# AdamDynamic_VCA-001.net
KiCad netlist of a schematic drawn in Altium Designer
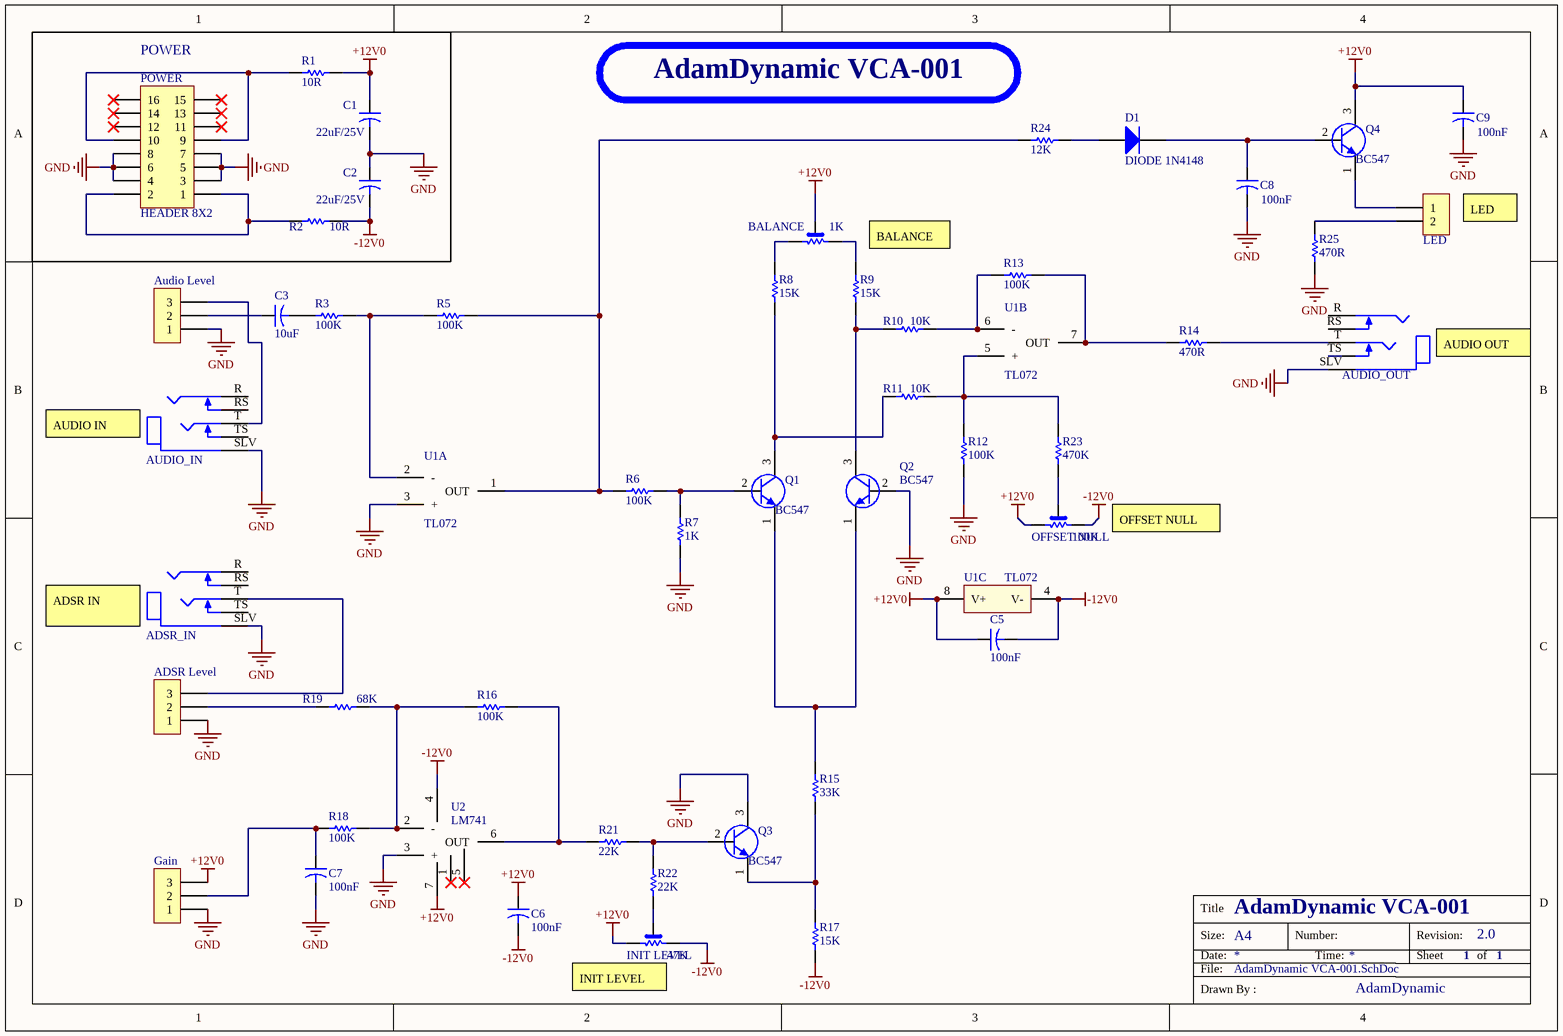
[diagram p0: AdamDynamic VCA-001.SchDoc]

(export (version "E")
  (design (tool "Eeschema 10.0.6"))
  (components
    (comp (ref "ADSR Level")
      (value "SCREW TERMINAL 3WAY")
      (footprint "SCREW TERMINAL 3WAY")
      (description "SCREW TERMINAL 3WAY 5.08mm")
      (libsource (lib "Integrated_Library1") (part "SCREW TERMINAL 3WAY"))
    )
    (comp (ref "ADSR_IN")
      (value "N114BPCX")
      (footprint "SWITCHCRAFT_N114BPCX")
      (description "Conn 1/4'' Phone Jack F 3 POS Solder ST Thru-Hole 5 Terminal 1 Port")
      (libsource (lib "112APCX") (part "N114BPCX"))
    )
    (comp (ref "Audio Level")
      (value "SCREW TERMINAL 3WAY")
      (footprint "SCREW TERMINAL 3WAY")
      (description "SCREW TERMINAL 3WAY 5.08mm")
      (libsource (lib "Integrated_Library1") (part "SCREW TERMINAL 3WAY"))
    )
    (comp (ref "AUDIO_IN")
      (value "N114BPCX")
      (footprint "SWITCHCRAFT_N114BPCX")
      (description "Conn 1/4'' Phone Jack F 3 POS Solder ST Thru-Hole 5 Terminal 1 Port")
      (libsource (lib "112APCX") (part "N114BPCX"))
    )
    (comp (ref "AUDIO_OUT")
      (value "N114BPCX")
      (footprint "SWITCHCRAFT_N114BPCX")
      (description "Conn 1/4'' Phone Jack F 3 POS Solder ST Thru-Hole 5 Terminal 1 Port")
      (libsource (lib "112APCX") (part "N114BPCX"))
    )
    (comp (ref "BALANCE")
      (value "1K")
      (footprint "RES VAR SQ")
      (description "Multiturn")
      (libsource (lib "Integrated_Library1") (part "ResTrimpot"))
    )
    (comp (ref "C1")
      (value "22uF/25V")
      (footprint "CAP 5X11")
      (libsource (lib "Integrated_Library1") (part "Capacitor Polar"))
    )
    (comp (ref "C2")
      (value "22uF/25V")
      (footprint "CAP 5X11")
      (libsource (lib "Integrated_Library1") (part "Capacitor Polar"))
    )
    (comp (ref "C3")
      (value "10uF")
      (footprint "CAP 5X11")
      (libsource (lib "Integrated_Library1") (part "Capacitor Polar"))
    )
    (comp (ref "C5")
      (value "100nF")
      (footprint "CAP RAD-0.3")
      (libsource (lib "Integrated_Library1") (part "Capacitor Polar"))
    )
    (comp (ref "C6")
      (value "100nF")
      (footprint "CAP RAD-0.3")
      (libsource (lib "Integrated_Library1") (part "Capacitor Polar"))
    )
    (comp (ref "C7")
      (value "100nF")
      (footprint "CAP RAD-0.3")
      (libsource (lib "Integrated_Library1") (part "Capacitor Polar"))
    )
    (comp (ref "C8")
      (value "100nF")
      (footprint "CAP RAD-0.3")
      (libsource (lib "Integrated_Library1") (part "Capacitor Polar"))
    )
    (comp (ref "C9")
      (value "100nF")
      (footprint "CAP RAD-0.3")
      (libsource (lib "Integrated_Library1") (part "Capacitor Polar"))
    )
    (comp (ref "D1")
      (value "DIODE 1N4148")
      (footprint "DO-35")
      (description "Small Signal Fast Switching Diodes")
      (libsource (lib "Integrated_Library1") (part "DIODE 1N4148"))
    )
    (comp (ref "Gain")
      (value "SCREW TERMINAL 3WAY")
      (footprint "SCREW TERMINAL 3WAY")
      (description "SCREW TERMINAL 3WAY 5.08mm")
      (libsource (lib "Integrated_Library1") (part "SCREW TERMINAL 3WAY"))
    )
    (comp (ref "INIT LEVEL")
      (value "47K")
      (footprint "RES VAR SQ")
      (description "Multiturn")
      (libsource (lib "Integrated_Library1") (part "ResTrimpot"))
    )
    (comp (ref "LED")
      (value "SCREW TERMINAL 2WAY")
      (footprint "SCREW TERMINAL 2WAY")
      (description "SCREW TERMINAL 2WAY 5.08mm")
      (libsource (lib "Integrated_Library1") (part "SCREW TERMINAL 2WAY"))
    )
    (comp (ref "OFFSET NULL")
      (value "100K")
      (footprint "RES VAR")
      (description "Multiturn")
      (libsource (lib "Integrated_Library1") (part "ResTrimpot"))
    )
    (comp (ref "POWER")
      (value "HEADER 8X2")
      (footprint "HEADER 8X2")
      (libsource (lib "Integrated_Library1") (part "HEADER 8X2"))
    )
    (comp (ref "Q1")
      (value "BC547")
      (footprint "TO92")
      (description "NPN Epitaxial Silicon Transistor")
      (libsource (lib "Integrated_Library1") (part "BC547"))
    )
    (comp (ref "Q2")
      (value "BC547")
      (footprint "TO92")
      (description "NPN Epitaxial Silicon Transistor")
      (libsource (lib "Integrated_Library1") (part "BC547"))
    )
    (comp (ref "Q3")
      (value "BC547")
      (footprint "TO92")
      (description "NPN Epitaxial Silicon Transistor")
      (libsource (lib "Integrated_Library1") (part "BC547"))
    )
    (comp (ref "Q4")
      (value "BC547")
      (footprint "TO92")
      (description "NPN Epitaxial Silicon Transistor")
      (libsource (lib "Integrated_Library1") (part "BC547"))
    )
    (comp (ref "R1")
      (value "10R")
      (footprint "RES 6.2 x 0.5 x 2.3")
      (description "Resistor")
      (fields (field (name "PUBLISHER") "Altium Limited"))
      (libsource (lib "Schlib1") (part "Res2"))
    )
    (comp (ref "R2")
      (value "10R")
      (footprint "RES 6.2 x 0.5 x 2.3")
      (description "Resistor")
      (fields (field (name "PUBLISHER") "Altium Limited"))
      (libsource (lib "Schlib1") (part "Res2"))
    )
    (comp (ref "R3")
      (value "100K")
      (footprint "RES 6.2 x 0.5 x 2.3")
      (description "Resistor")
      (fields (field (name "PUBLISHER") "Altium Limited"))
      (libsource (lib "Schlib1") (part "Res2"))
    )
    (comp (ref "R5")
      (value "100K")
      (footprint "RES 6.2 x 0.5 x 2.3")
      (description "Resistor")
      (fields (field (name "PUBLISHER") "Altium Limited"))
      (libsource (lib "Schlib1") (part "Res2"))
    )
    (comp (ref "R6")
      (value "100K")
      (footprint "RES 6.2 x 0.5 x 2.3")
      (description "Resistor")
      (fields (field (name "PUBLISHER") "Altium Limited"))
      (libsource (lib "Schlib1") (part "Res2"))
    )
    (comp (ref "R7")
      (value "1K")
      (footprint "RES 6.2 x 0.5 x 2.3")
      (description "Resistor")
      (fields (field (name "PUBLISHER") "Altium Limited"))
      (libsource (lib "Schlib1") (part "Res2"))
    )
    (comp (ref "R8")
      (value "15K")
      (footprint "RES 6.2 x 0.5 x 2.3")
      (description "Resistor")
      (fields (field (name "PUBLISHER") "Altium Limited"))
      (libsource (lib "Schlib1") (part "Res2"))
    )
    (comp (ref "R9")
      (value "15K")
      (footprint "RES 6.2 x 0.5 x 2.3")
      (description "Resistor")
      (fields (field (name "PUBLISHER") "Altium Limited"))
      (libsource (lib "Schlib1") (part "Res2"))
    )
    (comp (ref "R10")
      (value "10K")
      (footprint "RES 6.2 x 0.5 x 2.3")
      (description "Resistor")
      (fields (field (name "PUBLISHER") "Altium Limited"))
      (libsource (lib "Schlib1") (part "Res2"))
    )
    (comp (ref "R11")
      (value "10K")
      (footprint "RES 6.2 x 0.5 x 2.3")
      (description "Resistor")
      (fields (field (name "PUBLISHER") "Altium Limited"))
      (libsource (lib "Schlib1") (part "Res2"))
    )
    (comp (ref "R12")
      (value "100K")
      (footprint "RES 6.2 x 0.5 x 2.3")
      (description "Resistor")
      (fields (field (name "PUBLISHER") "Altium Limited"))
      (libsource (lib "Schlib1") (part "Res2"))
    )
    (comp (ref "R13")
      (value "100K")
      (footprint "RES 6.2 x 0.5 x 2.3")
      (description "Resistor")
      (fields (field (name "PUBLISHER") "Altium Limited"))
      (libsource (lib "Schlib1") (part "Res2"))
    )
    (comp (ref "R14")
      (value "470R")
      (footprint "RES 6.2 x 0.5 x 2.3")
      (description "Resistor")
      (fields (field (name "PUBLISHER") "Altium Limited"))
      (libsource (lib "Schlib1") (part "Res2"))
    )
    (comp (ref "R15")
      (value "33K")
      (footprint "RES 6.2 x 0.5 x 2.3")
      (description "Resistor")
      (fields (field (name "PUBLISHER") "Altium Limited"))
      (libsource (lib "Schlib1") (part "Res2"))
    )
    (comp (ref "R16")
      (value "100K")
      (footprint "RES 6.2 x 0.5 x 2.3")
      (description "Resistor")
      (fields (field (name "PUBLISHER") "Altium Limited"))
      (libsource (lib "Schlib1") (part "Res2"))
    )
    (comp (ref "R17")
      (value "15K")
      (footprint "RES 6.2 x 0.5 x 2.3")
      (description "Resistor")
      (fields (field (name "PUBLISHER") "Altium Limited"))
      (libsource (lib "Schlib1") (part "Res2"))
    )
    (comp (ref "R18")
      (value "100K")
      (footprint "RES 6.2 x 0.5 x 2.3")
      (description "Resistor")
      (fields (field (name "PUBLISHER") "Altium Limited"))
      (libsource (lib "Schlib1") (part "Res2"))
    )
    (comp (ref "R19")
      (value "68K")
      (footprint "RES 6.2 x 0.5 x 2.3")
      (description "Resistor")
      (fields (field (name "PUBLISHER") "Altium Limited"))
      (libsource (lib "Schlib1") (part "Res2"))
    )
    (comp (ref "R21")
      (value "22K")
      (footprint "RES 6.2 x 0.5 x 2.3")
      (description "Resistor")
      (fields (field (name "PUBLISHER") "Altium Limited"))
      (libsource (lib "Schlib1") (part "Res2"))
    )
    (comp (ref "R22")
      (value "22K")
      (footprint "RES 6.2 x 0.5 x 2.3")
      (description "Resistor")
      (fields (field (name "PUBLISHER") "Altium Limited"))
      (libsource (lib "Schlib1") (part "Res2"))
    )
    (comp (ref "R23")
      (value "470K")
      (footprint "RES 6.2 x 0.5 x 2.3")
      (description "Resistor")
      (fields (field (name "PUBLISHER") "Altium Limited"))
      (libsource (lib "Schlib1") (part "Res2"))
    )
    (comp (ref "R24")
      (value "12K")
      (footprint "RES 6.2 x 0.5 x 2.3")
      (description "Resistor")
      (fields (field (name "PUBLISHER") "Altium Limited"))
      (libsource (lib "Schlib1") (part "Res2"))
    )
    (comp (ref "R25")
      (value "470R")
      (footprint "RES 6.2 x 0.5 x 2.3")
      (description "Resistor")
      (fields (field (name "PUBLISHER") "Altium Limited"))
      (libsource (lib "Schlib1") (part "Res2"))
    )
    (comp (ref "U1")
      (value "TL072")
      (footprint "DIP 8 PIN")
      (description "Low-Noise FET-Input Operational Amplifiers")
      (libsource (lib "Integrated_Library1") (part "TL072"))
    )
    (comp (ref "U2")
      (value "LM741")
      (footprint "DIP 8 PIN")
      (libsource (lib "Integrated_Library1") (part "LM741"))
    )
  )
  (nets
    (net (code "1") (name "+12V0") (class "Default")
      (node (ref "BALANCE") (pin "2") (pinfunction "2_2") (pintype "passive"))
      (node (ref "C1") (pin "1") (pinfunction "1_1") (pintype "passive"))
      (node (ref "C5") (pin "1") (pinfunction "1_1") (pintype "passive"))
      (node (ref "C6") (pin "1") (pinfunction "1_1") (pintype "passive"))
      (node (ref "C9") (pin "1") (pinfunction "1_1") (pintype "passive"))
      (node (ref "Gain") (pin "3") (pinfunction "3_3") (pintype "passive"))
      (node (ref "INIT LEVEL") (pin "1") (pinfunction "1_1") (pintype "passive"))
      (node (ref "OFFSET NULL") (pin "1") (pinfunction "1_1") (pintype "passive"))
      (node (ref "Q4") (pin "3") (pinfunction "E_3") (pintype "passive"))
      (node (ref "R1") (pin "1") (pinfunction "1_1") (pintype "passive"))
      (node (ref "U1") (pin "8") (pinfunction "V+_8") (pintype "passive"))
      (node (ref "U2") (pin "7") (pintype "passive"))
    )
    (net (code "2") (name "-12V0") (class "Default")
      (node (ref "C2") (pin "2") (pinfunction "2_2") (pintype "passive"))
      (node (ref "C5") (pin "2") (pinfunction "2_2") (pintype "passive"))
      (node (ref "C6") (pin "2") (pinfunction "2_2") (pintype "passive"))
      (node (ref "INIT LEVEL") (pin "3") (pinfunction "3_3") (pintype "passive"))
      (node (ref "OFFSET NULL") (pin "3") (pinfunction "3_3") (pintype "passive"))
      (node (ref "R17") (pin "1") (pinfunction "1_1") (pintype "passive"))
      (node (ref "R2") (pin "1") (pinfunction "1_1") (pintype "passive"))
      (node (ref "U1") (pin "4") (pinfunction "V-_4") (pintype "passive"))
      (node (ref "U2") (pin "4") (pintype "passive"))
    )
    (net (code "3") (name "GND") (class "Default")
      (node (ref "ADSR Level") (pin "1") (pinfunction "1_1") (pintype "passive"))
      (node (ref "ADSR_IN") (pin "SLV") (pinfunction "SLEEVE_SLV") (pintype "passive"))
      (node (ref "AUDIO_IN") (pin "SLV") (pinfunction "SLEEVE_SLV") (pintype "passive"))
      (node (ref "AUDIO_OUT") (pin "SLV") (pinfunction "SLEEVE_SLV") (pintype "passive"))
      (node (ref "Audio Level") (pin "1") (pinfunction "1_1") (pintype "passive"))
      (node (ref "C1") (pin "2") (pinfunction "2_2") (pintype "passive"))
      (node (ref "C2") (pin "1") (pinfunction "1_1") (pintype "passive"))
      (node (ref "C7") (pin "2") (pinfunction "2_2") (pintype "passive"))
      (node (ref "C8") (pin "2") (pinfunction "2_2") (pintype "passive"))
      (node (ref "C9") (pin "2") (pinfunction "2_2") (pintype "passive"))
      (node (ref "Gain") (pin "1") (pinfunction "1_1") (pintype "passive"))
      (node (ref "POWER") (pin "3") (pinfunction "3_3") (pintype "passive"))
      (node (ref "POWER") (pin "4") (pinfunction "4_4") (pintype "passive"))
      (node (ref "POWER") (pin "5") (pinfunction "5_5") (pintype "passive"))
      (node (ref "POWER") (pin "6") (pinfunction "6_6") (pintype "passive"))
      (node (ref "POWER") (pin "7") (pinfunction "7_7") (pintype "passive"))
      (node (ref "POWER") (pin "8") (pinfunction "8_8") (pintype "passive"))
      (node (ref "Q2") (pin "2") (pinfunction "B_2") (pintype "passive"))
      (node (ref "Q3") (pin "3") (pinfunction "E_3") (pintype "passive"))
      (node (ref "R12") (pin "2") (pinfunction "2_2") (pintype "passive"))
      (node (ref "R25") (pin "2") (pinfunction "2_2") (pintype "passive"))
      (node (ref "R7") (pin "2") (pinfunction "2_2") (pintype "passive"))
      (node (ref "U1") (pin "3") (pinfunction "+_3") (pintype "passive"))
      (node (ref "U2") (pin "3") (pinfunction "+_3") (pintype "passive"))
    )
    (net (code "4") (name "Net-(ADSR Level-Pad2)") (class "Default")
      (node (ref "ADSR Level") (pin "2") (pinfunction "2_2") (pintype "passive"))
      (node (ref "R19") (pin "2") (pinfunction "2_2") (pintype "passive"))
    )
    (net (code "5") (name "Net-(ADSR_IN-TIP)") (class "Default")
      (node (ref "ADSR Level") (pin "3") (pinfunction "3_3") (pintype "passive"))
      (node (ref "ADSR_IN") (pin "T") (pinfunction "TIP_T") (pintype "passive"))
    )
    (net (code "6") (name "Net-(AUDIO_IN-TIP)") (class "Default")
      (node (ref "AUDIO_IN") (pin "T") (pinfunction "TIP_T") (pintype "passive"))
      (node (ref "Audio Level") (pin "3") (pinfunction "3_3") (pintype "passive"))
    )
    (net (code "7") (name "Net-(AUDIO_OUT-TIP)") (class "Default")
      (node (ref "AUDIO_OUT") (pin "T") (pinfunction "TIP_T") (pintype "passive"))
      (node (ref "R14") (pin "1") (pinfunction "1_1") (pintype "passive"))
    )
    (net (code "8") (name "Net-(Audio Level-Pad2)") (class "Default")
      (node (ref "Audio Level") (pin "2") (pinfunction "2_2") (pintype "passive"))
      (node (ref "C3") (pin "1") (pinfunction "1_1") (pintype "passive"))
    )
    (net (code "9") (name "Net-(BALANCE-Pad1)") (class "Default")
      (node (ref "BALANCE") (pin "1") (pinfunction "1_1") (pintype "passive"))
      (node (ref "R8") (pin "2") (pinfunction "2_2") (pintype "passive"))
    )
    (net (code "10") (name "Net-(BALANCE-Pad3)") (class "Default")
      (node (ref "BALANCE") (pin "3") (pinfunction "3_3") (pintype "passive"))
      (node (ref "R9") (pin "2") (pinfunction "2_2") (pintype "passive"))
    )
    (net (code "11") (name "Net-(C3-Pad2)") (class "Default")
      (node (ref "C3") (pin "2") (pinfunction "2_2") (pintype "passive"))
      (node (ref "R3") (pin "2") (pinfunction "2_2") (pintype "passive"))
    )
    (net (code "12") (name "Net-(C7-Pad1)") (class "Default")
      (node (ref "C7") (pin "1") (pinfunction "1_1") (pintype "passive"))
      (node (ref "Gain") (pin "2") (pinfunction "2_2") (pintype "passive"))
      (node (ref "R18") (pin "2") (pinfunction "2_2") (pintype "passive"))
    )
    (net (code "13") (name "Net-(D1-A)") (class "Default")
      (node (ref "D1") (pin "1") (pinfunction "A_1") (pintype "passive"))
      (node (ref "R24") (pin "1") (pinfunction "1_1") (pintype "passive"))
    )
    (net (code "14") (name "Net-(D1-K)") (class "Default")
      (node (ref "C8") (pin "1") (pinfunction "1_1") (pintype "passive"))
      (node (ref "D1") (pin "2") (pinfunction "K_2") (pintype "passive"))
      (node (ref "Q4") (pin "2") (pinfunction "B_2") (pintype "passive"))
    )
    (net (code "15") (name "Net-(INIT LEVEL-Pad2)") (class "Default")
      (node (ref "INIT LEVEL") (pin "2") (pinfunction "2_2") (pintype "passive"))
      (node (ref "R22") (pin "2") (pinfunction "2_2") (pintype "passive"))
    )
    (net (code "16") (name "Net-(LED-Pad2)") (class "Default")
      (node (ref "LED") (pin "2") (pinfunction "2_2") (pintype "passive"))
      (node (ref "R25") (pin "1") (pinfunction "1_1") (pintype "passive"))
    )
    (net (code "17") (name "Net-(OFFSET NULL-Pad2)") (class "Default")
      (node (ref "OFFSET NULL") (pin "2") (pinfunction "2_2") (pintype "passive"))
      (node (ref "R23") (pin "2") (pinfunction "2_2") (pintype "passive"))
    )
    (net (code "18") (name "Net-(POWER-Pad1)") (class "Default")
      (node (ref "POWER") (pin "1") (pinfunction "1_1") (pintype "passive"))
      (node (ref "POWER") (pin "2") (pinfunction "2_2") (pintype "passive"))
      (node (ref "R2") (pin "2") (pinfunction "2_2") (pintype "passive"))
    )
    (net (code "19") (name "Net-(POWER-Pad10)") (class "Default")
      (node (ref "POWER") (pin "10") (pinfunction "10_10") (pintype "passive"))
      (node (ref "POWER") (pin "9") (pinfunction "9_9") (pintype "passive"))
      (node (ref "R1") (pin "2") (pinfunction "2_2") (pintype "passive"))
    )
    (net (code "20") (name "Net-(Q1-B)") (class "Default")
      (node (ref "Q1") (pin "2") (pinfunction "B_2") (pintype "passive"))
      (node (ref "R6") (pin "1") (pinfunction "1_1") (pintype "passive"))
      (node (ref "R7") (pin "1") (pinfunction "1_1") (pintype "passive"))
    )
    (net (code "21") (name "Net-(Q1-C)") (class "Default")
      (node (ref "Q1") (pin "1") (pinfunction "C_1") (pintype "passive"))
      (node (ref "Q2") (pin "1") (pinfunction "C_1") (pintype "passive"))
      (node (ref "R15") (pin "2") (pinfunction "2_2") (pintype "passive"))
    )
    (net (code "22") (name "Net-(Q1-E)") (class "Default")
      (node (ref "Q1") (pin "3") (pinfunction "E_3") (pintype "passive"))
      (node (ref "R11") (pin "2") (pinfunction "2_2") (pintype "passive"))
      (node (ref "R8") (pin "1") (pinfunction "1_1") (pintype "passive"))
    )
    (net (code "23") (name "Net-(Q2-E)") (class "Default")
      (node (ref "Q2") (pin "3") (pinfunction "E_3") (pintype "passive"))
      (node (ref "R10") (pin "2") (pinfunction "2_2") (pintype "passive"))
      (node (ref "R9") (pin "1") (pinfunction "1_1") (pintype "passive"))
    )
    (net (code "24") (name "Net-(Q3-B)") (class "Default")
      (node (ref "Q3") (pin "2") (pinfunction "B_2") (pintype "passive"))
      (node (ref "R21") (pin "1") (pinfunction "1_1") (pintype "passive"))
      (node (ref "R22") (pin "1") (pinfunction "1_1") (pintype "passive"))
    )
    (net (code "25") (name "Net-(Q3-C)") (class "Default")
      (node (ref "Q3") (pin "1") (pinfunction "C_1") (pintype "passive"))
      (node (ref "R15") (pin "1") (pinfunction "1_1") (pintype "passive"))
      (node (ref "R17") (pin "2") (pinfunction "2_2") (pintype "passive"))
    )
    (net (code "26") (name "Net-(Q4-C)") (class "Default")
      (node (ref "LED") (pin "1") (pinfunction "1_1") (pintype "passive"))
      (node (ref "Q4") (pin "1") (pinfunction "C_1") (pintype "passive"))
    )
    (net (code "27") (name "Net-(U1A--)") (class "Default")
      (node (ref "R3") (pin "1") (pinfunction "1_1") (pintype "passive"))
      (node (ref "R5") (pin "2") (pinfunction "2_2") (pintype "passive"))
      (node (ref "U1") (pin "2") (pinfunction "-_2") (pintype "passive"))
    )
    (net (code "28") (name "Net-(U1A-OUT)") (class "Default")
      (node (ref "R24") (pin "2") (pinfunction "2_2") (pintype "passive"))
      (node (ref "R5") (pin "1") (pinfunction "1_1") (pintype "passive"))
      (node (ref "R6") (pin "2") (pinfunction "2_2") (pintype "passive"))
      (node (ref "U1") (pin "1") (pinfunction "OUT_1") (pintype "passive"))
    )
    (net (code "29") (name "Net-(U1B-+)") (class "Default")
      (node (ref "R11") (pin "1") (pinfunction "1_1") (pintype "passive"))
      (node (ref "R12") (pin "1") (pinfunction "1_1") (pintype "passive"))
      (node (ref "R23") (pin "1") (pinfunction "1_1") (pintype "passive"))
      (node (ref "U1") (pin "5") (pinfunction "+_5") (pintype "passive"))
    )
    (net (code "30") (name "Net-(U1B--)") (class "Default")
      (node (ref "R10") (pin "1") (pinfunction "1_1") (pintype "passive"))
      (node (ref "R13") (pin "2") (pinfunction "2_2") (pintype "passive"))
      (node (ref "U1") (pin "6") (pinfunction "-_6") (pintype "passive"))
    )
    (net (code "31") (name "Net-(U1B-OUT)") (class "Default")
      (node (ref "R13") (pin "1") (pinfunction "1_1") (pintype "passive"))
      (node (ref "R14") (pin "2") (pinfunction "2_2") (pintype "passive"))
      (node (ref "U1") (pin "7") (pinfunction "OUT_7") (pintype "passive"))
    )
    (net (code "32") (name "Net-(U2--)") (class "Default")
      (node (ref "R16") (pin "2") (pinfunction "2_2") (pintype "passive"))
      (node (ref "R18") (pin "1") (pinfunction "1_1") (pintype "passive"))
      (node (ref "R19") (pin "1") (pinfunction "1_1") (pintype "passive"))
      (node (ref "U2") (pin "2") (pinfunction "-_2") (pintype "passive"))
    )
    (net (code "33") (name "Net-(U2-OUT)") (class "Default")
      (node (ref "R16") (pin "1") (pinfunction "1_1") (pintype "passive"))
      (node (ref "R21") (pin "2") (pinfunction "2_2") (pintype "passive"))
      (node (ref "U2") (pin "6") (pinfunction "OUT_6") (pintype "passive"))
    )
    (net (code "34") (name "unconnected-(ADSR_IN-RING-PadR)") (class "Default")
      (node (ref "ADSR_IN") (pin "R") (pinfunction "RING_R") (pintype "passive"))
    )
    (net (code "35") (name "unconnected-(ADSR_IN-RING_SHUNT-PadRS)") (class "Default")
      (node (ref "ADSR_IN") (pin "RS") (pinfunction "RING_SHUNT_RS") (pintype "passive"))
    )
    (net (code "36") (name "unconnected-(ADSR_IN-TIP_SHUNT-PadTS)") (class "Default")
      (node (ref "ADSR_IN") (pin "TS") (pinfunction "TIP_SHUNT_TS") (pintype "passive"))
    )
    (net (code "37") (name "unconnected-(AUDIO_IN-RING-PadR)") (class "Default")
      (node (ref "AUDIO_IN") (pin "R") (pinfunction "RING_R") (pintype "passive"))
    )
    (net (code "38") (name "unconnected-(AUDIO_IN-RING_SHUNT-PadRS)") (class "Default")
      (node (ref "AUDIO_IN") (pin "RS") (pinfunction "RING_SHUNT_RS") (pintype "passive"))
    )
    (net (code "39") (name "unconnected-(AUDIO_IN-TIP_SHUNT-PadTS)") (class "Default")
      (node (ref "AUDIO_IN") (pin "TS") (pinfunction "TIP_SHUNT_TS") (pintype "passive"))
    )
    (net (code "40") (name "unconnected-(AUDIO_OUT-RING-PadR)") (class "Default")
      (node (ref "AUDIO_OUT") (pin "R") (pinfunction "RING_R") (pintype "passive"))
    )
    (net (code "41") (name "unconnected-(AUDIO_OUT-RING_SHUNT-PadRS)") (class "Default")
      (node (ref "AUDIO_OUT") (pin "RS") (pinfunction "RING_SHUNT_RS") (pintype "passive"))
    )
    (net (code "42") (name "unconnected-(AUDIO_OUT-TIP_SHUNT-PadTS)") (class "Default")
      (node (ref "AUDIO_OUT") (pin "TS") (pinfunction "TIP_SHUNT_TS") (pintype "passive"))
    )
    (net (code "43") (name "unconnected-(POWER-Pad11)") (class "Default")
      (node (ref "POWER") (pin "11") (pinfunction "11_11") (pintype "passive+no_connect"))
    )
    (net (code "44") (name "unconnected-(POWER-Pad12)") (class "Default")
      (node (ref "POWER") (pin "12") (pinfunction "12_12") (pintype "passive+no_connect"))
    )
    (net (code "45") (name "unconnected-(POWER-Pad13)") (class "Default")
      (node (ref "POWER") (pin "13") (pinfunction "13_13") (pintype "passive+no_connect"))
    )
    (net (code "46") (name "unconnected-(POWER-Pad14)") (class "Default")
      (node (ref "POWER") (pin "14") (pinfunction "14_14") (pintype "passive+no_connect"))
    )
    (net (code "47") (name "unconnected-(POWER-Pad15)") (class "Default")
      (node (ref "POWER") (pin "15") (pinfunction "15_15") (pintype "passive+no_connect"))
    )
    (net (code "48") (name "unconnected-(POWER-Pad16)") (class "Default")
      (node (ref "POWER") (pin "16") (pinfunction "16_16") (pintype "passive+no_connect"))
    )
    (net (code "49") (name "unconnected-(U2-Pad1)") (class "Default")
      (node (ref "U2") (pin "1") (pintype "passive+no_connect"))
    )
    (net (code "50") (name "unconnected-(U2-Pad5)") (class "Default")
      (node (ref "U2") (pin "5") (pintype "passive+no_connect"))
    )
  )
)
